# DCM_Flyback.net
KiCad netlist of a schematic drawn in Altium Designer
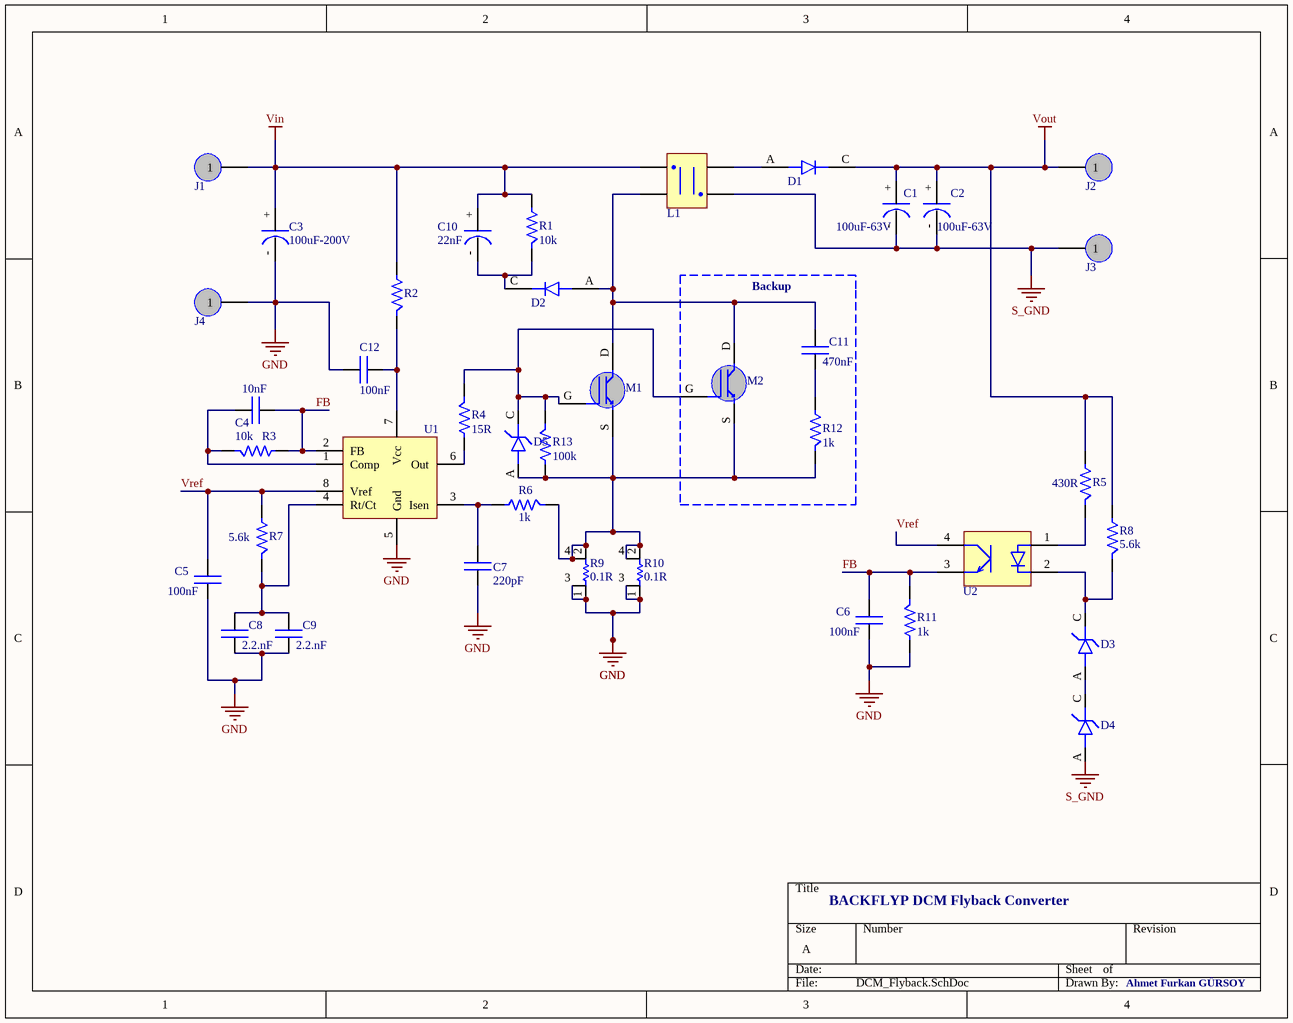
[diagram p0: DCM_Flyback.SchDoc]

(export (version "E")
  (design (tool "Eeschema 10.0.6"))
  (components
    (comp (ref "C1")
      (value "100uF-63V")
      (footprint "100uF-63V")
      (libsource (lib "Flyback_lib") (part "100uF-63V"))
    )
    (comp (ref "C2")
      (value "100uF-63V")
      (footprint "100uF-63V")
      (libsource (lib "Flyback_lib") (part "100uF-63V"))
    )
    (comp (ref "C3")
      (value "100uF-200V")
      (footprint "100uF-63V")
      (libsource (lib "Flyback_lib") (part "100uF-63V"))
    )
    (comp (ref "C4")
      (value "10nF")
      (footprint "Cap-lentil-100n")
      (libsource (lib "Flyback_lib") (part "Capacitor_lentil_100n"))
    )
    (comp (ref "C5")
      (value "100nF")
      (footprint "Cap-lentil-100n")
      (libsource (lib "Flyback_lib") (part "Capacitor_lentil_100n"))
    )
    (comp (ref "C6")
      (value "100nF")
      (footprint "Cap-lentil-100n")
      (libsource (lib "Flyback_lib") (part "Capacitor_lentil_100n"))
    )
    (comp (ref "C7")
      (value "220pF")
      (footprint "Cap-lentil-2.2n")
      (libsource (lib "Flyback_lib") (part "Cap-Lentil-2.2n"))
    )
    (comp (ref "C8")
      (value "2.2.nF")
      (footprint "Cap-lentil-2.2n")
      (libsource (lib "Flyback_lib") (part "Cap-Lentil-2.2n"))
    )
    (comp (ref "C9")
      (value "2.2.nF")
      (footprint "Cap-lentil-2.2n")
      (libsource (lib "Flyback_lib") (part "Cap-Lentil-2.2n"))
    )
    (comp (ref "C10") (value "22nF") (footprint "20uF-50V") (libsource (lib "Flyback_lib") (part "20uF-50V")))
    (comp (ref "C11")
      (value "470nF")
      (footprint "Cap-lentil-100n")
      (libsource (lib "Flyback_lib") (part "Capacitor_lentil_100n"))
    )
    (comp (ref "C12")
      (value "100nF")
      (footprint "Cap-lentil-2.2n")
      (libsource (lib "Flyback_lib") (part "Cap-Lentil-2.2n"))
    )
    (comp (ref "D1")
      (value "Secondary Diode")
      (footprint "MBR10150")
      (libsource (lib "Flyback_lib") (part "Secondary Diode"))
    )
    (comp (ref "D2")
      (value "Snubber Diode")
      (footprint "MBR10150")
      (libsource (lib "Flyback_lib") (part "Snubber Diode"))
    )
    (comp (ref "D3") (value "Zener") (footprint "Zener") (libsource (lib "Flyback_lib") (part "Zener")))
    (comp (ref "D4") (value "Zener") (footprint "Zener") (libsource (lib "Flyback_lib") (part "Zener")))
    (comp (ref "D5") (value "Zener") (footprint "Zener") (libsource (lib "Flyback_lib") (part "Zener")))
    (comp (ref "J1") (value "4mm Con") (footprint "Con-4mm") (libsource (lib "Flyback_lib") (part "4mm Con")))
    (comp (ref "J2") (value "4mm Con") (footprint "Con-4mm") (libsource (lib "Flyback_lib") (part "4mm Con")))
    (comp (ref "J3") (value "4mm Con") (footprint "Con-4mm") (libsource (lib "Flyback_lib") (part "4mm Con")))
    (comp (ref "J4") (value "4mm Con") (footprint "Con-4mm") (libsource (lib "Flyback_lib") (part "4mm Con")))
    (comp (ref "L1")
      (value "Transformer")
      (footprint "Transformer_EE3515")
      (libsource (lib "Flyback_lib") (part "Transformer"))
    )
    (comp (ref "M1") (value "MOSFET") (footprint "MOSFET") (libsource (lib "Flyback_lib") (part "MOSFET")))
    (comp (ref "M2")
      (value "IRFP250N")
      (footprint "TO247 with Heatsink")
      (libsource (lib "Flyback_lib") (part "IRFP250N"))
    )
    (comp (ref "R1")
      (value "10k")
      (footprint "StoneRes-5W")
      (libsource (lib "Flyback_lib") (part "StoneRes"))
    )
    (comp (ref "R2") (value "IncRes") (footprint "IncRes") (libsource (lib "Flyback_lib") (part "IncRes")))
    (comp (ref "R3") (value "10k") (footprint "IncRes") (libsource (lib "Flyback_lib") (part "IncRes")))
    (comp (ref "R4") (value "15R") (footprint "IncRes") (libsource (lib "Flyback_lib") (part "IncRes")))
    (comp (ref "R5") (value "430R") (footprint "Resistor") (libsource (lib "Flyback_lib") (part "Resistor")))
    (comp (ref "R6") (value "1k") (footprint "IncRes") (libsource (lib "Flyback_lib") (part "IncRes")))
    (comp (ref "R7") (value "5.6k") (footprint "IncRes") (libsource (lib "Flyback_lib") (part "IncRes")))
    (comp (ref "R8") (value "5.6k") (footprint "Resistor") (libsource (lib "Flyback_lib") (part "Resistor")))
    (comp (ref "R9")
      (value "0.1R")
      (footprint "ISB_SMT_V1_E")
      (description "RES SMD 2817 1% 5W C")
      (fields
        (field (name "MANUFACTURER") "Isabellenhutte")
        (field (name "SAPPARTNUMBER") "DSB")
        (field (name "CHECKED/REVISEDBY") "CYEGIN")
        (field (name "PUBLISHER") "PPOSPOS")
        (field (name "APPROVED") "EKARAGOZ")
      )
      (libsource (lib "T6A_Library") (part "ISB_RES-SMT"))
    )
    (comp (ref "R10")
      (value "0.1R")
      (footprint "ISB_SMT_V1_E")
      (description "RES SMD 2817 1% 5W C")
      (fields
        (field (name "MANUFACTURER") "Isabellenhutte")
        (field (name "SAPPARTNUMBER") "DSB")
        (field (name "CHECKED/REVISEDBY") "CYEGIN")
        (field (name "PUBLISHER") "PPOSPOS")
        (field (name "APPROVED") "EKARAGOZ")
      )
      (libsource (lib "T6A_Library") (part "ISB_RES-SMT"))
    )
    (comp (ref "R11") (value "1k") (footprint "IncRes") (libsource (lib "Flyback_lib") (part "IncRes")))
    (comp (ref "R12") (value "1k") (footprint "IncRes") (libsource (lib "Flyback_lib") (part "IncRes")))
    (comp (ref "R13") (value "100k") (footprint "IncRes") (libsource (lib "Flyback_lib") (part "IncRes")))
    (comp (ref "U1")
      (value "UC3843AD")
      (footprint "UC3843AD")
      (libsource (lib "Flyback_lib") (part "UC3843AD"))
    )
    (comp (ref "U2") (value "Opto") (footprint "Opto") (libsource (lib "Flyback_lib") (part "Opto")))
  )
  (nets
    (net (code "1") (name "/FB") (class "Default")
      (node (ref "C4") (pin "2") (pinfunction "2_2") (pintype "passive"))
      (node (ref "C6") (pin "1") (pinfunction "1_1") (pintype "passive"))
      (node (ref "R11") (pin "2") (pinfunction "2_2") (pintype "passive"))
      (node (ref "R3") (pin "1") (pinfunction "1_1") (pintype "passive"))
      (node (ref "U1") (pin "2") (pinfunction "FB_2") (pintype "passive"))
      (node (ref "U2") (pin "3") (pinfunction "E_3") (pintype "passive"))
    )
    (net (code "2") (name "/Vref") (class "Default")
      (node (ref "C5") (pin "1") (pinfunction "1_1") (pintype "passive"))
      (node (ref "R7") (pin "1") (pinfunction "1_1") (pintype "passive"))
      (node (ref "U1") (pin "8") (pinfunction "Vref_8") (pintype "passive"))
      (node (ref "U2") (pin "4") (pinfunction "Col_4") (pintype "passive"))
    )
    (net (code "3") (name "GND") (class "Default")
      (node (ref "C12") (pin "1") (pinfunction "1_1") (pintype "passive"))
      (node (ref "C3") (pin "-") (pinfunction "-_-") (pintype "passive"))
      (node (ref "C5") (pin "2") (pinfunction "2_2") (pintype "passive"))
      (node (ref "C6") (pin "2") (pinfunction "2_2") (pintype "passive"))
      (node (ref "C7") (pin "2") (pinfunction "2_2") (pintype "passive"))
      (node (ref "C8") (pin "2") (pinfunction "2_2") (pintype "passive"))
      (node (ref "C9") (pin "2") (pinfunction "2_2") (pintype "passive"))
      (node (ref "J4") (pin "1") (pinfunction "1_1") (pintype "passive"))
      (node (ref "R10") (pin "1") (pinfunction "1_1") (pintype "passive"))
      (node (ref "R10") (pin "3") (pinfunction "3_3") (pintype "passive"))
      (node (ref "R11") (pin "1") (pinfunction "1_1") (pintype "passive"))
      (node (ref "R9") (pin "1") (pinfunction "1_1") (pintype "passive"))
      (node (ref "R9") (pin "3") (pinfunction "3_3") (pintype "passive"))
      (node (ref "U1") (pin "5") (pinfunction "Gnd_5") (pintype "passive"))
    )
    (net (code "4") (name "Net-(C10-Pad-)") (class "Default")
      (node (ref "C10") (pin "-") (pinfunction "-_-") (pintype "passive"))
      (node (ref "D2") (pin "C") (pinfunction "C_C") (pintype "passive"))
      (node (ref "R1") (pin "2") (pinfunction "2_2") (pintype "passive"))
    )
    (net (code "5") (name "Net-(C11-Pad2)") (class "Default")
      (node (ref "C11") (pin "2") (pinfunction "2_2") (pintype "passive"))
      (node (ref "R12") (pin "1") (pinfunction "1_1") (pintype "passive"))
    )
    (net (code "6") (name "Net-(D3-PadA)") (class "Default")
      (node (ref "D3") (pin "A") (pinfunction "A_A") (pintype "passive"))
      (node (ref "D4") (pin "C") (pinfunction "C_C") (pintype "passive"))
    )
    (net (code "7") (name "Net-(D5-PadA)") (class "Default")
      (node (ref "D5") (pin "A") (pinfunction "A_A") (pintype "passive"))
      (node (ref "M1") (pin "S") (pinfunction "S_S") (pintype "passive"))
      (node (ref "M2") (pin "S") (pinfunction "S_S") (pintype "passive"))
      (node (ref "R10") (pin "2") (pinfunction "2_2") (pintype "passive"))
      (node (ref "R10") (pin "4") (pinfunction "4_4") (pintype "passive"))
      (node (ref "R12") (pin "2") (pinfunction "2_2") (pintype "passive"))
      (node (ref "R13") (pin "1") (pinfunction "1_1") (pintype "passive"))
      (node (ref "R6") (pin "2") (pinfunction "2_2") (pintype "passive"))
      (node (ref "R9") (pin "2") (pinfunction "2_2") (pintype "passive"))
      (node (ref "R9") (pin "4") (pinfunction "4_4") (pintype "passive"))
    )
    (net (code "8") (name "Net-(D5-PadC)") (class "Default")
      (node (ref "D5") (pin "C") (pinfunction "C_C") (pintype "passive"))
      (node (ref "M1") (pin "G") (pinfunction "G_G") (pintype "passive"))
      (node (ref "M2") (pin "G") (pinfunction "G_G") (pintype "passive"))
      (node (ref "R13") (pin "2") (pinfunction "2_2") (pintype "passive"))
      (node (ref "R4") (pin "2") (pinfunction "2_2") (pintype "passive"))
    )
    (net (code "9") (name "Net-(L1-1)") (class "Default")
      (node (ref "C11") (pin "1") (pinfunction "1_1") (pintype "passive"))
      (node (ref "D2") (pin "A") (pinfunction "A_A") (pintype "passive"))
      (node (ref "L1") (pin "2") (pinfunction "1_2") (pintype "passive"))
      (node (ref "M1") (pin "D") (pinfunction "D_D") (pintype "passive"))
      (node (ref "M2") (pin "D") (pinfunction "D_D") (pintype "passive"))
    )
    (net (code "10") (name "Net-(L1-2)") (class "Default")
      (node (ref "D1") (pin "A") (pinfunction "A_A") (pintype "passive"))
      (node (ref "L1") (pin "3") (pinfunction "2_3") (pintype "passive"))
    )
    (net (code "11") (name "Net-(U1-Comp)") (class "Default")
      (node (ref "C4") (pin "1") (pinfunction "1_1") (pintype "passive"))
      (node (ref "R3") (pin "2") (pinfunction "2_2") (pintype "passive"))
      (node (ref "U1") (pin "1") (pinfunction "Comp_1") (pintype "passive"))
    )
    (net (code "12") (name "Net-(U1-Isen)") (class "Default")
      (node (ref "C7") (pin "1") (pinfunction "1_1") (pintype "passive"))
      (node (ref "R6") (pin "1") (pinfunction "1_1") (pintype "passive"))
      (node (ref "U1") (pin "3") (pinfunction "Isen_3") (pintype "passive"))
    )
    (net (code "13") (name "Net-(U1-Out)") (class "Default")
      (node (ref "R4") (pin "1") (pinfunction "1_1") (pintype "passive"))
      (node (ref "U1") (pin "6") (pinfunction "Out_6") (pintype "passive"))
    )
    (net (code "14") (name "Net-(U1-Rt{slash}Ct)") (class "Default")
      (node (ref "C8") (pin "1") (pinfunction "1_1") (pintype "passive"))
      (node (ref "C9") (pin "1") (pinfunction "1_1") (pintype "passive"))
      (node (ref "R7") (pin "2") (pinfunction "2_2") (pintype "passive"))
      (node (ref "U1") (pin "4") (pinfunction "Rt/Ct_4") (pintype "passive"))
    )
    (net (code "15") (name "Net-(U1-Vcc)") (class "Default")
      (node (ref "C12") (pin "2") (pinfunction "2_2") (pintype "passive"))
      (node (ref "R2") (pin "2") (pinfunction "2_2") (pintype "passive"))
      (node (ref "U1") (pin "7") (pinfunction "Vcc_7") (pintype "passive"))
    )
    (net (code "16") (name "Net-(U2-A)") (class "Default")
      (node (ref "R5") (pin "2") (pinfunction "2_2") (pintype "passive"))
      (node (ref "U2") (pin "1") (pinfunction "A_1") (pintype "passive"))
    )
    (net (code "17") (name "Net-(U2-C)") (class "Default")
      (node (ref "D3") (pin "C") (pinfunction "C_C") (pintype "passive"))
      (node (ref "R8") (pin "2") (pinfunction "2_2") (pintype "passive"))
      (node (ref "U2") (pin "2") (pinfunction "C_2") (pintype "passive"))
    )
    (net (code "18") (name "S_GND") (class "Default")
      (node (ref "C1") (pin "-") (pinfunction "-_-") (pintype "passive"))
      (node (ref "C2") (pin "-") (pinfunction "-_-") (pintype "passive"))
      (node (ref "D4") (pin "A") (pinfunction "A_A") (pintype "passive"))
      (node (ref "J3") (pin "1") (pinfunction "1_1") (pintype "passive"))
      (node (ref "L1") (pin "4") (pinfunction "3_4") (pintype "passive"))
    )
    (net (code "19") (name "Vin") (class "Default")
      (node (ref "C10") (pin "+") (pinfunction "+_+") (pintype "passive"))
      (node (ref "C3") (pin "+") (pinfunction "+_+") (pintype "passive"))
      (node (ref "J1") (pin "1") (pinfunction "1_1") (pintype "passive"))
      (node (ref "L1") (pin "1") (pinfunction "0_1") (pintype "passive"))
      (node (ref "R1") (pin "1") (pinfunction "1_1") (pintype "passive"))
      (node (ref "R2") (pin "1") (pinfunction "1_1") (pintype "passive"))
    )
    (net (code "20") (name "Vout") (class "Default")
      (node (ref "C1") (pin "+") (pinfunction "+_+") (pintype "passive"))
      (node (ref "C2") (pin "+") (pinfunction "+_+") (pintype "passive"))
      (node (ref "D1") (pin "C") (pinfunction "C_C") (pintype "passive"))
      (node (ref "J2") (pin "1") (pinfunction "1_1") (pintype "passive"))
      (node (ref "R5") (pin "1") (pinfunction "1_1") (pintype "passive"))
      (node (ref "R8") (pin "1") (pinfunction "1_1") (pintype "passive"))
    )
  )
)
